# edison_misc.net
KiCad netlist of a schematic drawn in Altium Designer
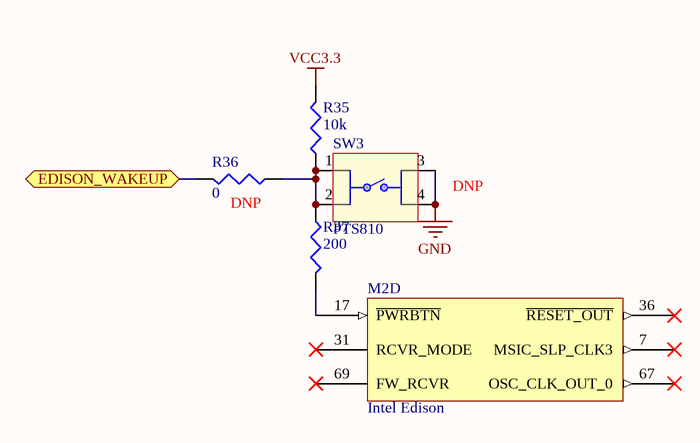
[diagram p0: edison_misc.SchDoc]

(export (version "E")
  (design (tool "Eeschema 10.0.6"))
  (components
    (comp (ref "M2")
      (value "Intel Edison")
      (footprint "Intel Edison mating")
      (libsource (lib "Intel Edison") (part "Intel Edison"))
    )
    (comp (ref "R35")
      (value "10k")
      (footprint "0402")
      (description "RES SMD 10K OHM 1% 1/16W 0402")
      (fields (field (name "TOLERANCE") "1%") (field (name "POWER") "1/16 W"))
      (libsource (lib "resistors") (part "CRCW040210K0FKED"))
    )
    (comp (ref "R36")
      (value "0")
      (footprint "0402")
      (description "RES SMD 0.0 OHM JUMPER 1/5W 0402")
      (fields
        (field (name "MANUFACTURER PART NUMBER") "CRCW04020000Z0EDHP")
        (field (name "MANUFACTURER") "Vishay Dale")
        (field (name "NOTE") "DNP")
      )
      (libsource (lib "resistors") (part "CRCW04020000Z0EDHP"))
    )
    (comp (ref "R37")
      (value "200")
      (footprint "0402")
      (description "RES SMD 200 OHM 1% 1/16W 0402")
      (fields (field (name "TOLERANCE") "1%") (field (name "POWER") "1/16 W"))
      (libsource (lib "resistors") (part "CRCW0402200RFKED"))
    )
    (comp (ref "SW3")
      (value "PTS810")
      (footprint "PTS810")
      (description "Tactile Switches")
      (fields (field (name "NOTE") "DNP"))
      (libsource (lib "switches") (part "PTS810"))
    )
  )
  (nets
    (net (code "1") (name "/EDISON_WAKEUP") (class "Default")
      (node (ref "R36") (pin "1") (pintype "passive"))
    )
    (net (code "2") (name "GND") (class "Default")
      (node (ref "SW3") (pin "3") (pinfunction "3_3") (pintype "passive"))
      (node (ref "SW3") (pin "4") (pinfunction "4_4") (pintype "passive"))
    )
    (net (code "3") (name "Net-(M2D-~{PWRBTN})") (class "Default")
      (node (ref "M2") (pin "17") (pinfunction "~{PWRBTN}_17") (pintype "input"))
      (node (ref "R37") (pin "1") (pintype "passive"))
    )
    (net (code "4") (name "Net-(R35-Pad2)") (class "Default")
      (node (ref "R35") (pin "2") (pintype "passive"))
      (node (ref "R36") (pin "2") (pintype "passive"))
      (node (ref "R37") (pin "2") (pintype "passive"))
      (node (ref "SW3") (pin "1") (pinfunction "1_1") (pintype "passive"))
      (node (ref "SW3") (pin "2") (pinfunction "2_2") (pintype "passive"))
    )
    (net (code "5") (name "VCC3.3") (class "Default") (node (ref "R35") (pin "1") (pintype "passive")))
    (net (code "6") (name "unconnected-(M2D-FW_RCVR-Pad69)") (class "Default")
      (node (ref "M2") (pin "69") (pinfunction "FW_RCVR_69") (pintype "passive+no_connect"))
    )
    (net (code "7") (name "unconnected-(M2D-MSIC_SLP_CLK3-Pad7)") (class "Default")
      (node (ref "M2") (pin "7") (pinfunction "MSIC_SLP_CLK3_7") (pintype "output+no_connect"))
    )
    (net (code "8") (name "unconnected-(M2D-OSC_CLK_OUT_0-Pad67)") (class "Default")
      (node (ref "M2") (pin "67") (pinfunction "OSC_CLK_OUT_0_67") (pintype "output+no_connect"))
    )
    (net (code "9") (name "unconnected-(M2D-RCVR_MODE-Pad31)") (class "Default")
      (node (ref "M2") (pin "31") (pinfunction "RCVR_MODE_31") (pintype "passive+no_connect"))
    )
    (net (code "10") (name "unconnected-(M2D-~{RESET_OUT}-Pad36)") (class "Default")
      (node (ref "M2") (pin "36") (pinfunction "~{RESET_OUT}_36") (pintype "output+no_connect"))
    )
  )
)
